# Sheet1.net
KiCad netlist of a schematic drawn in Altium Designer
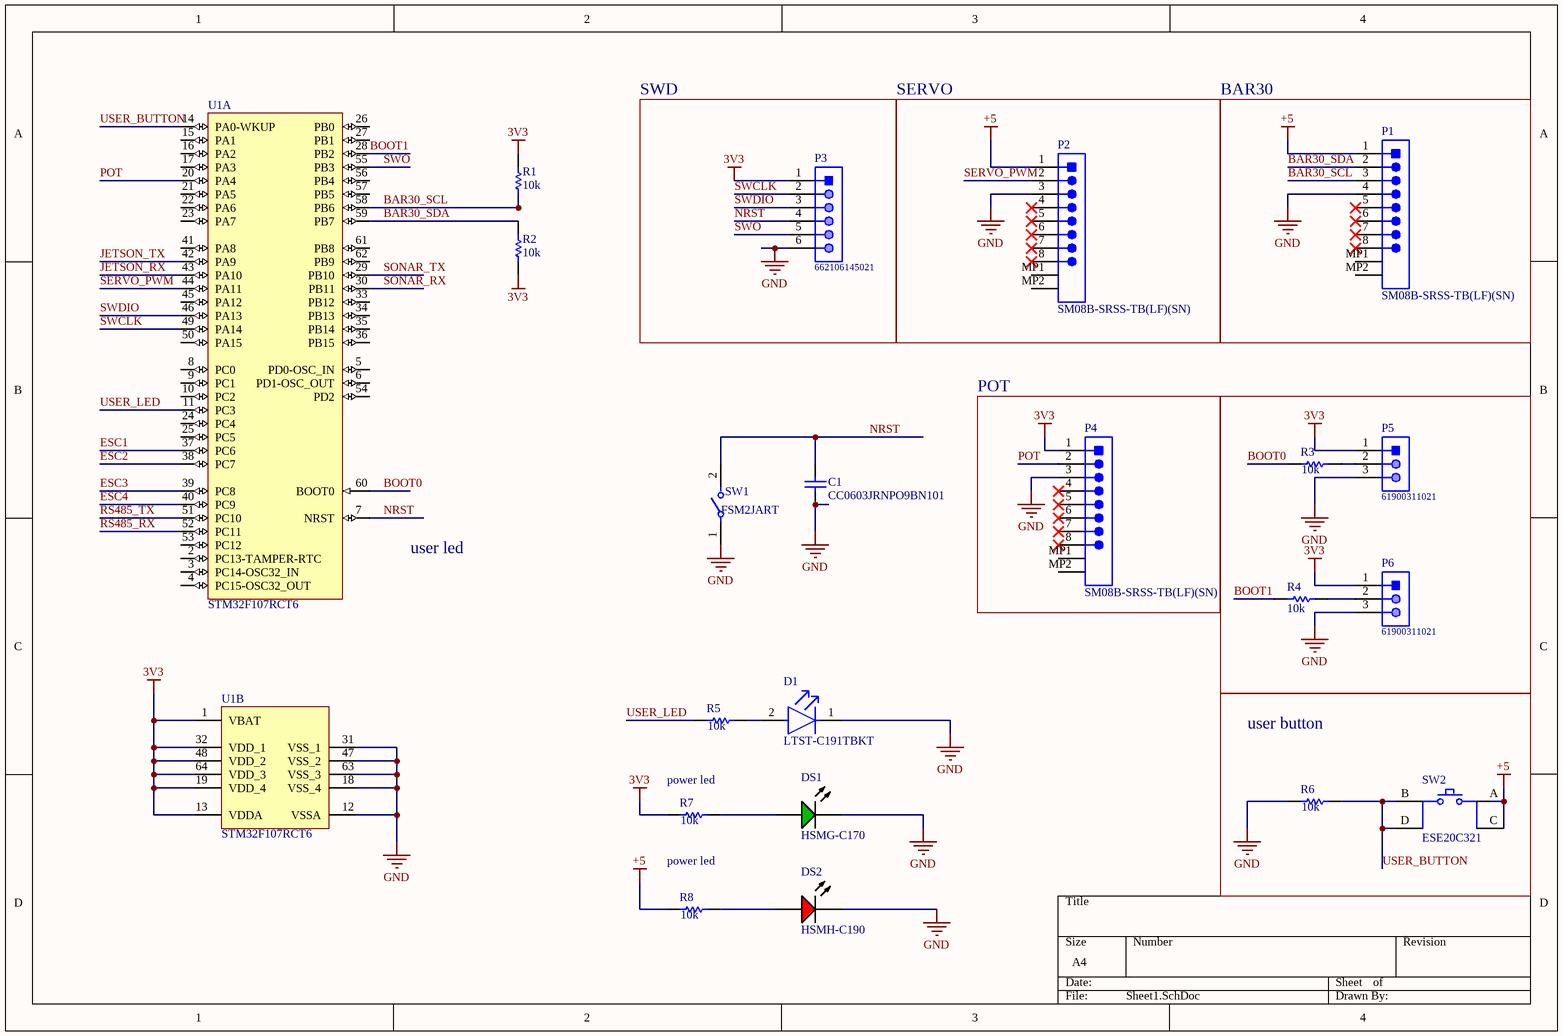
[diagram p0: Sheet1.SchDoc]

(export (version "E")
  (design (tool "Eeschema 10.0.6"))
  (components
    (comp (ref "C1")
      (value "CC0603JRNPO9BN101")
      (footprint "CAPC1608X90X40ML10T20")
      (description "Chip Capacitor, 100 pF, +/- 5%, 50 V, -55 to 125 degC, 0603 (1608 Metric), RoHS, Tape and Reel")
      (fields (field (name "TOLERANCE") "5%") (field (name "VOLTAGE") "50V"))
      (libsource (lib "Altium Content Vault") (part "CAP-NP-2"))
    )
    (comp (ref "D1")
      (value "LTST-C191TBKT")
      (footprint "FP-LTST-C191TBKT-MFG")
      (description "LED BLUE CLEAR CHIP SMD")
      (libsource (lib "Altium Content Vault") (part "8706943c75ba83719d021d2fdc84c58"))
    )
    (comp (ref "DS1")
      (value "HSMG-C170")
      (footprint "AVAG-HSMX-C170_V")
      (description "Chip LED, Green, 2.2 V, -40 to 85 degC, 2-Pin SMD, Pb-Free, Tape and Reel")
      (fields (field (name "MANUFACTURER") "Avago"))
      (libsource (lib "Altium Content Vault") (part "LED_GREEN_A1K2-2"))
    )
    (comp (ref "DS2")
      (value "HSMH-C190")
      (footprint "AVAG-HSMX-C190_V")
      (description "LED Uni-Color Red, 65 mW, 20 mA, -40 to 85 degC, 2-Pin SMD, RoHS, Tape and Reel")
      (libsource (lib "Altium Content Vault") (part "LED-RED-AK-2"))
    )
    (comp (ref "P1")
      (value "SM08B-SRSS-TB(LF)(SN)")
      (footprint "JST-SM08B-SRSS-TB_V")
      (description "Male Header, Pitch 1 mm, 1 x 8 Position, Height 2.95 mm, -25 to 85 degC, RoHS, Tape and Reel")
      (fields (field (name "MANUFACTURER") "JST"))
      (libsource (lib "Altium Content Vault") (part "CN-1P-2M-R8"))
    )
    (comp (ref "P2")
      (value "SM08B-SRSS-TB(LF)(SN)")
      (footprint "JST-SM08B-SRSS-TB_V")
      (description "Male Header, Pitch 1 mm, 1 x 8 Position, Height 2.95 mm, -25 to 85 degC, RoHS, Tape and Reel")
      (fields (field (name "MANUFACTURER") "JST"))
      (libsource (lib "Altium Content Vault") (part "CN-1P-2M-R8"))
    )
    (comp (ref "P3")
      (value "662106145021")
      (footprint "662106145021")
      (description "SMT Male Header WR-MPC3, with SMT Solder Tabs, Right Angled, Single Row, pitch 3 mm, 6 pins")
      (fields (field (name "MANUFACTURER") "Wurth Elektronik") (field (name "PUBLISHER") "WurthElektronik"))
      (libsource (lib "Altium Content Vault") (part "WE-CN-1P-M-R6"))
    )
    (comp (ref "P4")
      (value "SM08B-SRSS-TB(LF)(SN)")
      (footprint "JST-SM08B-SRSS-TB_V")
      (description "Male Header, Pitch 1 mm, 1 x 8 Position, Height 2.95 mm, -25 to 85 degC, RoHS, Tape and Reel")
      (fields (field (name "MANUFACTURER") "JST"))
      (libsource (lib "Altium Content Vault") (part "CN-1P-2M-R8"))
    )
    (comp (ref "P5")
      (value "61900311021")
      (footprint "61900311021")
      (description "Male Bottom Locking Header WR-WTB, THT, Right Angled, pitch 2.54 mm, 1 x 3 position")
      (fields (field (name "MANUFACTURER") "Wurth Elektronik") (field (name "PUBLISHER") "WurthElektronik"))
      (libsource (lib "Altium Content Vault") (part "WE-CN-1P-M-R3"))
    )
    (comp (ref "P6")
      (value "61900311021")
      (footprint "61900311021")
      (description "Male Bottom Locking Header WR-WTB, THT, Right Angled, pitch 2.54 mm, 1 x 3 position")
      (fields (field (name "MANUFACTURER") "Wurth Elektronik") (field (name "PUBLISHER") "WurthElektronik"))
      (libsource (lib "Altium Content Vault") (part "WE-CN-1P-M-R3"))
    )
    (comp (ref "R1")
      (value "10k")
      (footprint "RESC1609X50X30LL8T20")
      (description "Chip Resistor, 10 KOhm, +/- 1%, 100 mW, -55 to 155 degC, 0603 (1608 Metric), RoHS, Tape and Reel")
      (fields (field (name "MANUFACTURER") "Vishay Semiconductor"))
      (libsource (lib "Altium Content Vault") (part "RES-2"))
    )
    (comp (ref "R2")
      (value "10k")
      (footprint "RESC1609X50X30LL8T20")
      (description "Chip Resistor, 10 KOhm, +/- 1%, 100 mW, -55 to 155 degC, 0603 (1608 Metric), RoHS, Tape and Reel")
      (fields (field (name "MANUFACTURER") "Vishay Semiconductor"))
      (libsource (lib "Altium Content Vault") (part "RES-2"))
    )
    (comp (ref "R3")
      (value "10k")
      (footprint "RESC1609X50X30LL8T20")
      (description "Chip Resistor, 10 KOhm, +/- 1%, 100 mW, -55 to 155 degC, 0603 (1608 Metric), RoHS, Tape and Reel")
      (fields (field (name "MANUFACTURER") "Vishay Semiconductor"))
      (libsource (lib "Altium Content Vault") (part "RES-2"))
    )
    (comp (ref "R4")
      (value "10k")
      (footprint "RESC1609X50X30LL8T20")
      (description "Chip Resistor, 10 KOhm, +/- 1%, 100 mW, -55 to 155 degC, 0603 (1608 Metric), RoHS, Tape and Reel")
      (fields (field (name "MANUFACTURER") "Vishay Semiconductor"))
      (libsource (lib "Altium Content Vault") (part "RES-2"))
    )
    (comp (ref "R5")
      (value "10k")
      (footprint "RESC1609X50X30LL8T20")
      (description "Chip Resistor, 10 KOhm, +/- 1%, 100 mW, -55 to 155 degC, 0603 (1608 Metric), RoHS, Tape and Reel")
      (fields (field (name "MANUFACTURER") "Vishay Semiconductor"))
      (libsource (lib "Altium Content Vault") (part "RES-2"))
    )
    (comp (ref "R6")
      (value "10k")
      (footprint "RESC1609X50X30LL8T20")
      (description "Chip Resistor, 10 KOhm, +/- 1%, 100 mW, -55 to 155 degC, 0603 (1608 Metric), RoHS, Tape and Reel")
      (fields (field (name "MANUFACTURER") "Vishay Semiconductor"))
      (libsource (lib "Altium Content Vault") (part "RES-2"))
    )
    (comp (ref "R7")
      (value "10k")
      (footprint "RESC1609X50X30LL8T20")
      (description "Chip Resistor, 10 KOhm, +/- 1%, 100 mW, -55 to 155 degC, 0603 (1608 Metric), RoHS, Tape and Reel")
      (fields (field (name "MANUFACTURER") "Vishay Semiconductor"))
      (libsource (lib "Altium Content Vault") (part "RES-2"))
    )
    (comp (ref "R8")
      (value "10k")
      (footprint "RESC1609X50X30LL8T20")
      (description "Chip Resistor, 10 KOhm, +/- 1%, 100 mW, -55 to 155 degC, 0603 (1608 Metric), RoHS, Tape and Reel")
      (fields (field (name "MANUFACTURER") "Vishay Semiconductor"))
      (libsource (lib "Altium Content Vault") (part "RES-2"))
    )
    (comp (ref "SW1")
      (value "FSM2JART")
      (footprint "FP-FSM2JART-MFG")
      (description "SWITCH TACTILE SPST-NO 0.05A 12V")
      (libsource (lib "Altium Content Vault") (part "bb27bde45df87f1f469753f287ef5ae"))
    )
    (comp (ref "SW2")
      (value "ESE20C321")
      (footprint "FP-ESE20C321-MFG")
      (description "SWITCH PUSH SPST-NO 0.1A 14V")
      (libsource (lib "Altium Content Vault") (part "5c536a8a9a742c9a0b47ba8f96ce97a"))
    )
    (comp (ref "U1")
      (value "STM32F107RCT6")
      (footprint "STM-LQFP64_M")
      (libsource (lib "Altium Content Vault") (part "MC-ARM-STM32F10X-SQ64"))
    )
  )
  (nets
    (net (code "1") (name "+5") (class "Default")
      (node (ref "P1") (pin "1") (pinfunction "1_1") (pintype "passive"))
      (node (ref "P2") (pin "1") (pinfunction "1_1") (pintype "passive"))
      (node (ref "R8") (pin "1") (pinfunction "1_1") (pintype "passive"))
      (node (ref "SW2") (pin "A") (pinfunction "A_A") (pintype "passive"))
      (node (ref "SW2") (pin "C") (pinfunction "C_C") (pintype "passive"))
    )
    (net (code "2") (name "/BAR30_SCL") (class "Default")
      (node (ref "P1") (pin "3") (pinfunction "3_3") (pintype "passive"))
      (node (ref "R1") (pin "1") (pinfunction "1_1") (pintype "passive"))
      (node (ref "U1") (pin "58") (pinfunction "PB6_58") (pintype "bidirectional"))
    )
    (net (code "3") (name "/BAR30_SDA") (class "Default")
      (node (ref "P1") (pin "2") (pinfunction "2_2") (pintype "passive"))
      (node (ref "R2") (pin "2") (pinfunction "2_2") (pintype "passive"))
      (node (ref "U1") (pin "59") (pinfunction "PB7_59") (pintype "bidirectional"))
    )
    (net (code "4") (name "/BOOT0") (class "Default")
      (node (ref "R3") (pin "1") (pinfunction "1_1") (pintype "passive"))
      (node (ref "U1") (pin "60") (pinfunction "BOOT0_60") (pintype "input"))
    )
    (net (code "5") (name "/BOOT1") (class "Default")
      (node (ref "R4") (pin "1") (pinfunction "1_1") (pintype "passive"))
      (node (ref "U1") (pin "28") (pinfunction "PB2_28") (pintype "bidirectional"))
    )
    (net (code "6") (name "/ESC1") (class "Default")
      (node (ref "U1") (pin "37") (pinfunction "PC6_37") (pintype "bidirectional"))
    )
    (net (code "7") (name "/ESC2") (class "Default")
      (node (ref "U1") (pin "38") (pinfunction "PC7_38") (pintype "bidirectional"))
    )
    (net (code "8") (name "/ESC3") (class "Default")
      (node (ref "U1") (pin "39") (pinfunction "PC8_39") (pintype "bidirectional"))
    )
    (net (code "9") (name "/ESC4") (class "Default")
      (node (ref "U1") (pin "40") (pinfunction "PC9_40") (pintype "bidirectional"))
    )
    (net (code "10") (name "/JETSON_RX") (class "Default")
      (node (ref "U1") (pin "43") (pinfunction "PA10_43") (pintype "bidirectional"))
    )
    (net (code "11") (name "/JETSON_TX") (class "Default")
      (node (ref "U1") (pin "42") (pinfunction "PA9_42") (pintype "bidirectional"))
    )
    (net (code "12") (name "/NRST") (class "Default")
      (node (ref "C1") (pin "2") (pinfunction "2_2") (pintype "passive"))
      (node (ref "P3") (pin "4") (pinfunction "4_4") (pintype "passive"))
      (node (ref "SW1") (pin "2") (pinfunction "2_2") (pintype "passive"))
      (node (ref "U1") (pin "7") (pinfunction "NRST_7") (pintype "bidirectional"))
    )
    (net (code "13") (name "/POT") (class "Default")
      (node (ref "P4") (pin "2") (pinfunction "2_2") (pintype "passive"))
      (node (ref "U1") (pin "20") (pinfunction "PA4_20") (pintype "bidirectional"))
    )
    (net (code "14") (name "/RS485_RX") (class "Default")
      (node (ref "U1") (pin "52") (pinfunction "PC11_52") (pintype "bidirectional"))
    )
    (net (code "15") (name "/RS485_TX") (class "Default")
      (node (ref "U1") (pin "51") (pinfunction "PC10_51") (pintype "bidirectional"))
    )
    (net (code "16") (name "/SERVO_PWM") (class "Default")
      (node (ref "P2") (pin "2") (pinfunction "2_2") (pintype "passive"))
      (node (ref "U1") (pin "44") (pinfunction "PA11_44") (pintype "bidirectional"))
    )
    (net (code "17") (name "/SONAR_RX") (class "Default")
      (node (ref "U1") (pin "30") (pinfunction "PB11_30") (pintype "bidirectional"))
    )
    (net (code "18") (name "/SONAR_TX") (class "Default")
      (node (ref "U1") (pin "29") (pinfunction "PB10_29") (pintype "bidirectional"))
    )
    (net (code "19") (name "/SWCLK") (class "Default")
      (node (ref "P3") (pin "2") (pinfunction "2_2") (pintype "passive"))
      (node (ref "U1") (pin "49") (pinfunction "PA14_49") (pintype "bidirectional"))
    )
    (net (code "20") (name "/SWDIO") (class "Default")
      (node (ref "P3") (pin "3") (pinfunction "3_3") (pintype "passive"))
      (node (ref "U1") (pin "46") (pinfunction "PA13_46") (pintype "bidirectional"))
    )
    (net (code "21") (name "/SWO") (class "Default")
      (node (ref "P3") (pin "5") (pinfunction "5_5") (pintype "passive"))
      (node (ref "U1") (pin "55") (pinfunction "PB3_55") (pintype "bidirectional"))
    )
    (net (code "22") (name "/USER_BUTTON") (class "Default")
      (node (ref "R6") (pin "2") (pinfunction "2_2") (pintype "passive"))
      (node (ref "SW2") (pin "B") (pinfunction "B_B") (pintype "passive"))
      (node (ref "SW2") (pin "D") (pinfunction "D_D") (pintype "passive"))
      (node (ref "U1") (pin "14") (pinfunction "PA0-WKUP_14") (pintype "bidirectional"))
    )
    (net (code "23") (name "/USER_LED") (class "Default")
      (node (ref "R5") (pin "1") (pinfunction "1_1") (pintype "passive"))
      (node (ref "U1") (pin "11") (pinfunction "PC3_11") (pintype "bidirectional"))
    )
    (net (code "24") (name "3V3") (class "Default")
      (node (ref "P3") (pin "1") (pinfunction "1_1") (pintype "passive"))
      (node (ref "P4") (pin "1") (pinfunction "1_1") (pintype "passive"))
      (node (ref "P5") (pin "1") (pinfunction "1_1") (pintype "passive"))
      (node (ref "P6") (pin "1") (pinfunction "1_1") (pintype "passive"))
      (node (ref "R1") (pin "2") (pinfunction "2_2") (pintype "passive"))
      (node (ref "R2") (pin "1") (pinfunction "1_1") (pintype "passive"))
      (node (ref "R7") (pin "1") (pinfunction "1_1") (pintype "passive"))
      (node (ref "U1") (pin "1") (pinfunction "VBAT_1") (pintype "power_in"))
      (node (ref "U1") (pin "13") (pinfunction "VDDA_13") (pintype "power_in"))
      (node (ref "U1") (pin "19") (pinfunction "VDD_4_19") (pintype "power_in"))
      (node (ref "U1") (pin "32") (pinfunction "VDD_1_32") (pintype "power_in"))
      (node (ref "U1") (pin "48") (pinfunction "VDD_2_48") (pintype "power_in"))
      (node (ref "U1") (pin "64") (pinfunction "VDD_3_64") (pintype "power_in"))
    )
    (net (code "25") (name "GND") (class "Default")
      (node (ref "C1") (pin "1") (pinfunction "1_1") (pintype "passive"))
      (node (ref "D1") (pin "1") (pinfunction "C_1") (pintype "passive"))
      (node (ref "DS1") (pin "2") (pinfunction "K_2") (pintype "passive"))
      (node (ref "DS2") (pin "2") (pinfunction "K_2") (pintype "passive"))
      (node (ref "P1") (pin "4") (pinfunction "4_4") (pintype "passive"))
      (node (ref "P2") (pin "3") (pinfunction "3_3") (pintype "passive"))
      (node (ref "P3") (pin "6") (pinfunction "6_6") (pintype "passive"))
      (node (ref "P4") (pin "3") (pinfunction "3_3") (pintype "passive"))
      (node (ref "P5") (pin "3") (pinfunction "3_3") (pintype "passive"))
      (node (ref "P6") (pin "3") (pinfunction "3_3") (pintype "passive"))
      (node (ref "R6") (pin "1") (pinfunction "1_1") (pintype "passive"))
      (node (ref "SW1") (pin "1") (pinfunction "1_1") (pintype "passive"))
      (node (ref "U1") (pin "12") (pinfunction "VSSA_12") (pintype "power_in"))
      (node (ref "U1") (pin "18") (pinfunction "VSS_4_18") (pintype "power_in"))
      (node (ref "U1") (pin "31") (pinfunction "VSS_1_31") (pintype "power_in"))
      (node (ref "U1") (pin "47") (pinfunction "VSS_2_47") (pintype "power_in"))
      (node (ref "U1") (pin "63") (pinfunction "VSS_3_63") (pintype "power_in"))
    )
    (net (code "26") (name "Net-(D1-A)") (class "Default")
      (node (ref "D1") (pin "2") (pinfunction "A_2") (pintype "passive"))
      (node (ref "R5") (pin "2") (pinfunction "2_2") (pintype "passive"))
    )
    (net (code "27") (name "Net-(DS1-A)") (class "Default")
      (node (ref "DS1") (pin "1") (pinfunction "A_1") (pintype "passive"))
      (node (ref "R7") (pin "2") (pinfunction "2_2") (pintype "passive"))
    )
    (net (code "28") (name "Net-(DS2-A)") (class "Default")
      (node (ref "DS2") (pin "1") (pinfunction "A_1") (pintype "passive"))
      (node (ref "R8") (pin "2") (pinfunction "2_2") (pintype "passive"))
    )
    (net (code "29") (name "Net-(P5-Pad2)") (class "Default")
      (node (ref "P5") (pin "2") (pinfunction "2_2") (pintype "passive"))
      (node (ref "R3") (pin "2") (pinfunction "2_2") (pintype "passive"))
    )
    (net (code "30") (name "Net-(P6-Pad2)") (class "Default")
      (node (ref "P6") (pin "2") (pinfunction "2_2") (pintype "passive"))
      (node (ref "R4") (pin "2") (pinfunction "2_2") (pintype "passive"))
    )
    (net (code "31") (name "unconnected-(P1-Pad5)") (class "Default")
      (node (ref "P1") (pin "5") (pinfunction "5_5") (pintype "passive+no_connect"))
    )
    (net (code "32") (name "unconnected-(P1-Pad6)") (class "Default")
      (node (ref "P1") (pin "6") (pinfunction "6_6") (pintype "passive+no_connect"))
    )
    (net (code "33") (name "unconnected-(P1-Pad7)") (class "Default")
      (node (ref "P1") (pin "7") (pinfunction "7_7") (pintype "passive+no_connect"))
    )
    (net (code "34") (name "unconnected-(P1-Pad8)") (class "Default")
      (node (ref "P1") (pin "8") (pinfunction "8_8") (pintype "passive+no_connect"))
    )
    (net (code "35") (name "unconnected-(P1-PadMP1)") (class "Default")
      (node (ref "P1") (pin "MP1") (pinfunction "MP1_MP1") (pintype "passive"))
    )
    (net (code "36") (name "unconnected-(P1-PadMP2)") (class "Default")
      (node (ref "P1") (pin "MP2") (pinfunction "MP2_MP2") (pintype "passive"))
    )
    (net (code "37") (name "unconnected-(P2-Pad4)") (class "Default")
      (node (ref "P2") (pin "4") (pinfunction "4_4") (pintype "passive+no_connect"))
    )
    (net (code "38") (name "unconnected-(P2-Pad5)") (class "Default")
      (node (ref "P2") (pin "5") (pinfunction "5_5") (pintype "passive+no_connect"))
    )
    (net (code "39") (name "unconnected-(P2-Pad6)") (class "Default")
      (node (ref "P2") (pin "6") (pinfunction "6_6") (pintype "passive+no_connect"))
    )
    (net (code "40") (name "unconnected-(P2-Pad7)") (class "Default")
      (node (ref "P2") (pin "7") (pinfunction "7_7") (pintype "passive+no_connect"))
    )
    (net (code "41") (name "unconnected-(P2-Pad8)") (class "Default")
      (node (ref "P2") (pin "8") (pinfunction "8_8") (pintype "passive+no_connect"))
    )
    (net (code "42") (name "unconnected-(P2-PadMP1)") (class "Default")
      (node (ref "P2") (pin "MP1") (pinfunction "MP1_MP1") (pintype "passive"))
    )
    (net (code "43") (name "unconnected-(P2-PadMP2)") (class "Default")
      (node (ref "P2") (pin "MP2") (pinfunction "MP2_MP2") (pintype "passive"))
    )
    (net (code "44") (name "unconnected-(P4-Pad4)") (class "Default")
      (node (ref "P4") (pin "4") (pinfunction "4_4") (pintype "passive+no_connect"))
    )
    (net (code "45") (name "unconnected-(P4-Pad5)") (class "Default")
      (node (ref "P4") (pin "5") (pinfunction "5_5") (pintype "passive+no_connect"))
    )
    (net (code "46") (name "unconnected-(P4-Pad6)") (class "Default")
      (node (ref "P4") (pin "6") (pinfunction "6_6") (pintype "passive+no_connect"))
    )
    (net (code "47") (name "unconnected-(P4-Pad7)") (class "Default")
      (node (ref "P4") (pin "7") (pinfunction "7_7") (pintype "passive+no_connect"))
    )
    (net (code "48") (name "unconnected-(P4-Pad8)") (class "Default")
      (node (ref "P4") (pin "8") (pinfunction "8_8") (pintype "passive+no_connect"))
    )
    (net (code "49") (name "unconnected-(P4-PadMP1)") (class "Default")
      (node (ref "P4") (pin "MP1") (pinfunction "MP1_MP1") (pintype "passive"))
    )
    (net (code "50") (name "unconnected-(P4-PadMP2)") (class "Default")
      (node (ref "P4") (pin "MP2") (pinfunction "MP2_MP2") (pintype "passive"))
    )
    (net (code "51") (name "unconnected-(U1A-PA1-Pad15)") (class "Default")
      (node (ref "U1") (pin "15") (pinfunction "PA1_15") (pintype "bidirectional"))
    )
    (net (code "52") (name "unconnected-(U1A-PA2-Pad16)") (class "Default")
      (node (ref "U1") (pin "16") (pinfunction "PA2_16") (pintype "bidirectional"))
    )
    (net (code "53") (name "unconnected-(U1A-PA3-Pad17)") (class "Default")
      (node (ref "U1") (pin "17") (pinfunction "PA3_17") (pintype "bidirectional"))
    )
    (net (code "54") (name "unconnected-(U1A-PA5-Pad21)") (class "Default")
      (node (ref "U1") (pin "21") (pinfunction "PA5_21") (pintype "bidirectional"))
    )
    (net (code "55") (name "unconnected-(U1A-PA6-Pad22)") (class "Default")
      (node (ref "U1") (pin "22") (pinfunction "PA6_22") (pintype "bidirectional"))
    )
    (net (code "56") (name "unconnected-(U1A-PA7-Pad23)") (class "Default")
      (node (ref "U1") (pin "23") (pinfunction "PA7_23") (pintype "bidirectional"))
    )
    (net (code "57") (name "unconnected-(U1A-PA8-Pad41)") (class "Default")
      (node (ref "U1") (pin "41") (pinfunction "PA8_41") (pintype "bidirectional"))
    )
    (net (code "58") (name "unconnected-(U1A-PA12-Pad45)") (class "Default")
      (node (ref "U1") (pin "45") (pinfunction "PA12_45") (pintype "bidirectional"))
    )
    (net (code "59") (name "unconnected-(U1A-PA15-Pad50)") (class "Default")
      (node (ref "U1") (pin "50") (pinfunction "PA15_50") (pintype "bidirectional"))
    )
    (net (code "60") (name "unconnected-(U1A-PB0-Pad26)") (class "Default")
      (node (ref "U1") (pin "26") (pinfunction "PB0_26") (pintype "bidirectional"))
    )
    (net (code "61") (name "unconnected-(U1A-PB1-Pad27)") (class "Default")
      (node (ref "U1") (pin "27") (pinfunction "PB1_27") (pintype "bidirectional"))
    )
    (net (code "62") (name "unconnected-(U1A-PB4-Pad56)") (class "Default")
      (node (ref "U1") (pin "56") (pinfunction "PB4_56") (pintype "bidirectional"))
    )
    (net (code "63") (name "unconnected-(U1A-PB5-Pad57)") (class "Default")
      (node (ref "U1") (pin "57") (pinfunction "PB5_57") (pintype "bidirectional"))
    )
    (net (code "64") (name "unconnected-(U1A-PB8-Pad61)") (class "Default")
      (node (ref "U1") (pin "61") (pinfunction "PB8_61") (pintype "bidirectional"))
    )
    (net (code "65") (name "unconnected-(U1A-PB9-Pad62)") (class "Default")
      (node (ref "U1") (pin "62") (pinfunction "PB9_62") (pintype "bidirectional"))
    )
    (net (code "66") (name "unconnected-(U1A-PB12-Pad33)") (class "Default")
      (node (ref "U1") (pin "33") (pinfunction "PB12_33") (pintype "bidirectional"))
    )
    (net (code "67") (name "unconnected-(U1A-PB13-Pad34)") (class "Default")
      (node (ref "U1") (pin "34") (pinfunction "PB13_34") (pintype "bidirectional"))
    )
    (net (code "68") (name "unconnected-(U1A-PB14-Pad35)") (class "Default")
      (node (ref "U1") (pin "35") (pinfunction "PB14_35") (pintype "bidirectional"))
    )
    (net (code "69") (name "unconnected-(U1A-PB15-Pad36)") (class "Default")
      (node (ref "U1") (pin "36") (pinfunction "PB15_36") (pintype "bidirectional"))
    )
    (net (code "70") (name "unconnected-(U1A-PC0-Pad8)") (class "Default")
      (node (ref "U1") (pin "8") (pinfunction "PC0_8") (pintype "bidirectional"))
    )
    (net (code "71") (name "unconnected-(U1A-PC1-Pad9)") (class "Default")
      (node (ref "U1") (pin "9") (pinfunction "PC1_9") (pintype "bidirectional"))
    )
    (net (code "72") (name "unconnected-(U1A-PC2-Pad10)") (class "Default")
      (node (ref "U1") (pin "10") (pinfunction "PC2_10") (pintype "bidirectional"))
    )
    (net (code "73") (name "unconnected-(U1A-PC4-Pad24)") (class "Default")
      (node (ref "U1") (pin "24") (pinfunction "PC4_24") (pintype "bidirectional"))
    )
    (net (code "74") (name "unconnected-(U1A-PC5-Pad25)") (class "Default")
      (node (ref "U1") (pin "25") (pinfunction "PC5_25") (pintype "bidirectional"))
    )
    (net (code "75") (name "unconnected-(U1A-PC12-Pad53)") (class "Default")
      (node (ref "U1") (pin "53") (pinfunction "PC12_53") (pintype "bidirectional"))
    )
    (net (code "76") (name "unconnected-(U1A-PC13-TAMPER-RTC-Pad2)") (class "Default")
      (node (ref "U1") (pin "2") (pinfunction "PC13-TAMPER-RTC_2") (pintype "bidirectional"))
    )
    (net (code "77") (name "unconnected-(U1A-PC14-OSC32_IN-Pad3)") (class "Default")
      (node (ref "U1") (pin "3") (pinfunction "PC14-OSC32_IN_3") (pintype "bidirectional"))
    )
    (net (code "78") (name "unconnected-(U1A-PC15-OSC32_OUT-Pad4)") (class "Default")
      (node (ref "U1") (pin "4") (pinfunction "PC15-OSC32_OUT_4") (pintype "bidirectional"))
    )
    (net (code "79") (name "unconnected-(U1A-PD0-OSC_IN-Pad5)") (class "Default")
      (node (ref "U1") (pin "5") (pinfunction "PD0-OSC_IN_5") (pintype "bidirectional"))
    )
    (net (code "80") (name "unconnected-(U1A-PD1-OSC_OUT-Pad6)") (class "Default")
      (node (ref "U1") (pin "6") (pinfunction "PD1-OSC_OUT_6") (pintype "bidirectional"))
    )
    (net (code "81") (name "unconnected-(U1A-PD2-Pad54)") (class "Default")
      (node (ref "U1") (pin "54") (pinfunction "PD2_54") (pintype "bidirectional"))
    )
  )
)
